# JTAG_chain.net
KiCad netlist of a schematic drawn in Altium Designer
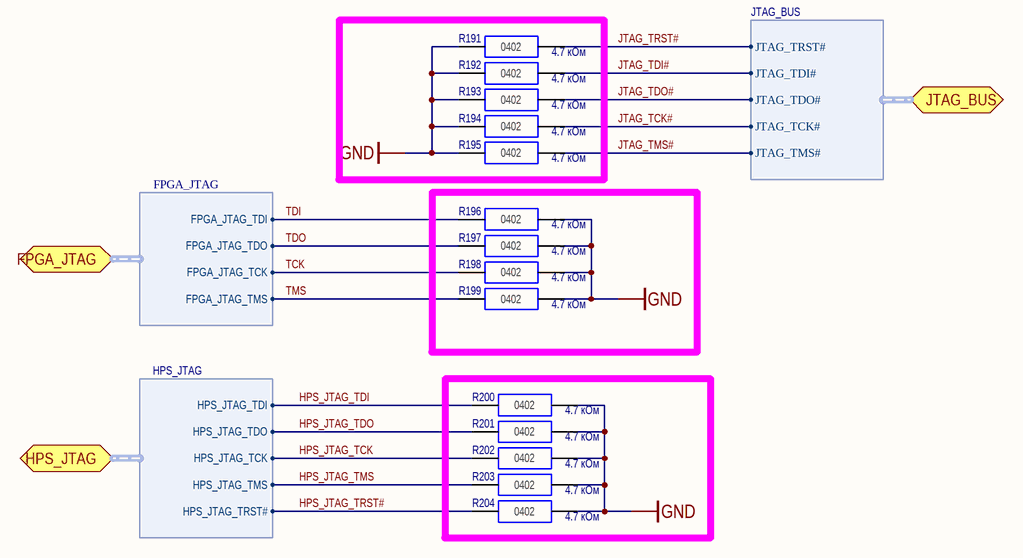
[diagram p0: JTAG_chain.SchDoc]

(export (version "E")
  (design (tool "Eeschema 10.0.6"))
  (components
    (comp (ref "R191")
      (value "4.7 кОм")
      (footprint "CR0402(1005)")
      (description "Чип резистор")
      (fields (field (name "TOLERANCE") "5%") (field (name "Comment") "CR0402-4.7 кОм-±5%"))
      (libsource (lib "Резисторы") (part "CR0402-#-±5%"))
    )
    (comp (ref "R192")
      (value "4.7 кОм")
      (footprint "CR0402(1005)")
      (description "Чип резистор")
      (fields (field (name "TOLERANCE") "5%") (field (name "Comment") "CR0402-4.7 кОм-±5%"))
      (libsource (lib "Резисторы") (part "CR0402-#-±5%"))
    )
    (comp (ref "R193")
      (value "4.7 кОм")
      (footprint "CR0402(1005)")
      (description "Чип резистор")
      (fields (field (name "TOLERANCE") "5%") (field (name "Comment") "CR0402-4.7 кОм-±5%"))
      (libsource (lib "Резисторы") (part "CR0402-#-±5%"))
    )
    (comp (ref "R194")
      (value "4.7 кОм")
      (footprint "CR0402(1005)")
      (description "Чип резистор")
      (fields (field (name "TOLERANCE") "5%") (field (name "Comment") "CR0402-4.7 кОм-±5%"))
      (libsource (lib "Резисторы") (part "CR0402-#-±5%"))
    )
    (comp (ref "R195")
      (value "4.7 кОм")
      (footprint "CR0402(1005)")
      (description "Чип резистор")
      (fields (field (name "TOLERANCE") "5%") (field (name "Comment") "CR0402-4.7 кОм-±5%"))
      (libsource (lib "Резисторы") (part "CR0402-#-±5%"))
    )
    (comp (ref "R196")
      (value "4.7 кОм")
      (footprint "CR0402(1005)")
      (description "Чип резистор")
      (fields (field (name "TOLERANCE") "5%") (field (name "Comment") "CR0402-4.7 кОм-±5%"))
      (libsource (lib "Резисторы") (part "CR0402-#-±5%"))
    )
    (comp (ref "R197")
      (value "4.7 кОм")
      (footprint "CR0402(1005)")
      (description "Чип резистор")
      (fields (field (name "TOLERANCE") "5%") (field (name "Comment") "CR0402-4.7 кОм-±5%"))
      (libsource (lib "Резисторы") (part "CR0402-#-±5%"))
    )
    (comp (ref "R198")
      (value "4.7 кОм")
      (footprint "CR0402(1005)")
      (description "Чип резистор")
      (fields (field (name "TOLERANCE") "5%") (field (name "Comment") "CR0402-4.7 кОм-±5%"))
      (libsource (lib "Резисторы") (part "CR0402-#-±5%"))
    )
    (comp (ref "R199")
      (value "4.7 кОм")
      (footprint "CR0402(1005)")
      (description "Чип резистор")
      (fields (field (name "TOLERANCE") "5%") (field (name "Comment") "CR0402-4.7 кОм-±5%"))
      (libsource (lib "Резисторы") (part "CR0402-#-±5%"))
    )
    (comp (ref "R200")
      (value "4.7 кОм")
      (footprint "CR0402(1005)")
      (description "Чип резистор")
      (fields (field (name "TOLERANCE") "5%") (field (name "Comment") "CR0402-4.7 кОм-±5%"))
      (libsource (lib "Резисторы") (part "CR0402-#-±5%"))
    )
    (comp (ref "R201")
      (value "4.7 кОм")
      (footprint "CR0402(1005)")
      (description "Чип резистор")
      (fields (field (name "TOLERANCE") "5%") (field (name "Comment") "CR0402-4.7 кОм-±5%"))
      (libsource (lib "Резисторы") (part "CR0402-#-±5%"))
    )
    (comp (ref "R202")
      (value "4.7 кОм")
      (footprint "CR0402(1005)")
      (description "Чип резистор")
      (fields (field (name "TOLERANCE") "5%") (field (name "Comment") "CR0402-4.7 кОм-±5%"))
      (libsource (lib "Резисторы") (part "CR0402-#-±5%"))
    )
    (comp (ref "R203")
      (value "4.7 кОм")
      (footprint "CR0402(1005)")
      (description "Чип резистор")
      (fields (field (name "TOLERANCE") "5%") (field (name "Comment") "CR0402-4.7 кОм-±5%"))
      (libsource (lib "Резисторы") (part "CR0402-#-±5%"))
    )
    (comp (ref "R204")
      (value "4.7 кОм")
      (footprint "CR0402(1005)")
      (description "Чип резистор")
      (fields (field (name "TOLERANCE") "5%") (field (name "Comment") "CR0402-4.7 кОм-±5%"))
      (libsource (lib "Резисторы") (part "CR0402-#-±5%"))
    )
  )
  (nets
    (net (code "4") (name "/HPS_JTAG_TCK") (class "Default")
      (node (ref "R202") (pin "1") (pinfunction "+_1") (pintype "passive"))
    )
    (net (code "5") (name "/HPS_JTAG_TDI") (class "Default")
      (node (ref "R200") (pin "1") (pinfunction "+_1") (pintype "passive"))
    )
    (net (code "6") (name "/HPS_JTAG_TDO") (class "Default")
      (node (ref "R201") (pin "1") (pinfunction "+_1") (pintype "passive"))
    )
    (net (code "7") (name "/HPS_JTAG_TMS") (class "Default")
      (node (ref "R203") (pin "1") (pinfunction "+_1") (pintype "passive"))
    )
    (net (code "8") (name "/HPS_JTAG_TRST#") (class "Default")
      (node (ref "R204") (pin "1") (pinfunction "+_1") (pintype "passive"))
    )
    (net (code "9") (name "/JTAG_TCK#") (class "Default")
      (node (ref "R194") (pin "2") (pinfunction "-_2") (pintype "passive"))
    )
    (net (code "10") (name "/JTAG_TDI#") (class "Default")
      (node (ref "R192") (pin "2") (pinfunction "-_2") (pintype "passive"))
    )
    (net (code "11") (name "/JTAG_TDO#") (class "Default")
      (node (ref "R193") (pin "2") (pinfunction "-_2") (pintype "passive"))
    )
    (net (code "12") (name "/JTAG_TMS#") (class "Default")
      (node (ref "R195") (pin "2") (pinfunction "-_2") (pintype "passive"))
    )
    (net (code "13") (name "/JTAG_TRST#") (class "Default")
      (node (ref "R191") (pin "2") (pinfunction "-_2") (pintype "passive"))
    )
    (net (code "14") (name "/TCK") (class "Default")
      (node (ref "R198") (pin "1") (pinfunction "+_1") (pintype "passive"))
    )
    (net (code "15") (name "/TDI") (class "Default")
      (node (ref "R196") (pin "1") (pinfunction "+_1") (pintype "passive"))
    )
    (net (code "16") (name "/TDO") (class "Default")
      (node (ref "R197") (pin "1") (pinfunction "+_1") (pintype "passive"))
    )
    (net (code "17") (name "/TMS") (class "Default")
      (node (ref "R199") (pin "1") (pinfunction "+_1") (pintype "passive"))
    )
    (net (code "21") (name "GND") (class "Default")
      (node (ref "R191") (pin "1") (pinfunction "+_1") (pintype "passive"))
      (node (ref "R192") (pin "1") (pinfunction "+_1") (pintype "passive"))
      (node (ref "R193") (pin "1") (pinfunction "+_1") (pintype "passive"))
      (node (ref "R194") (pin "1") (pinfunction "+_1") (pintype "passive"))
      (node (ref "R195") (pin "1") (pinfunction "+_1") (pintype "passive"))
      (node (ref "R196") (pin "2") (pinfunction "-_2") (pintype "passive"))
      (node (ref "R197") (pin "2") (pinfunction "-_2") (pintype "passive"))
      (node (ref "R198") (pin "2") (pinfunction "-_2") (pintype "passive"))
      (node (ref "R199") (pin "2") (pinfunction "-_2") (pintype "passive"))
      (node (ref "R200") (pin "2") (pinfunction "-_2") (pintype "passive"))
      (node (ref "R201") (pin "2") (pinfunction "-_2") (pintype "passive"))
      (node (ref "R202") (pin "2") (pinfunction "-_2") (pintype "passive"))
      (node (ref "R203") (pin "2") (pinfunction "-_2") (pintype "passive"))
      (node (ref "R204") (pin "2") (pinfunction "-_2") (pintype "passive"))
    )
  )
)
